# SCHEMA.net
KiCad netlist of a schematic drawn in EAGLE
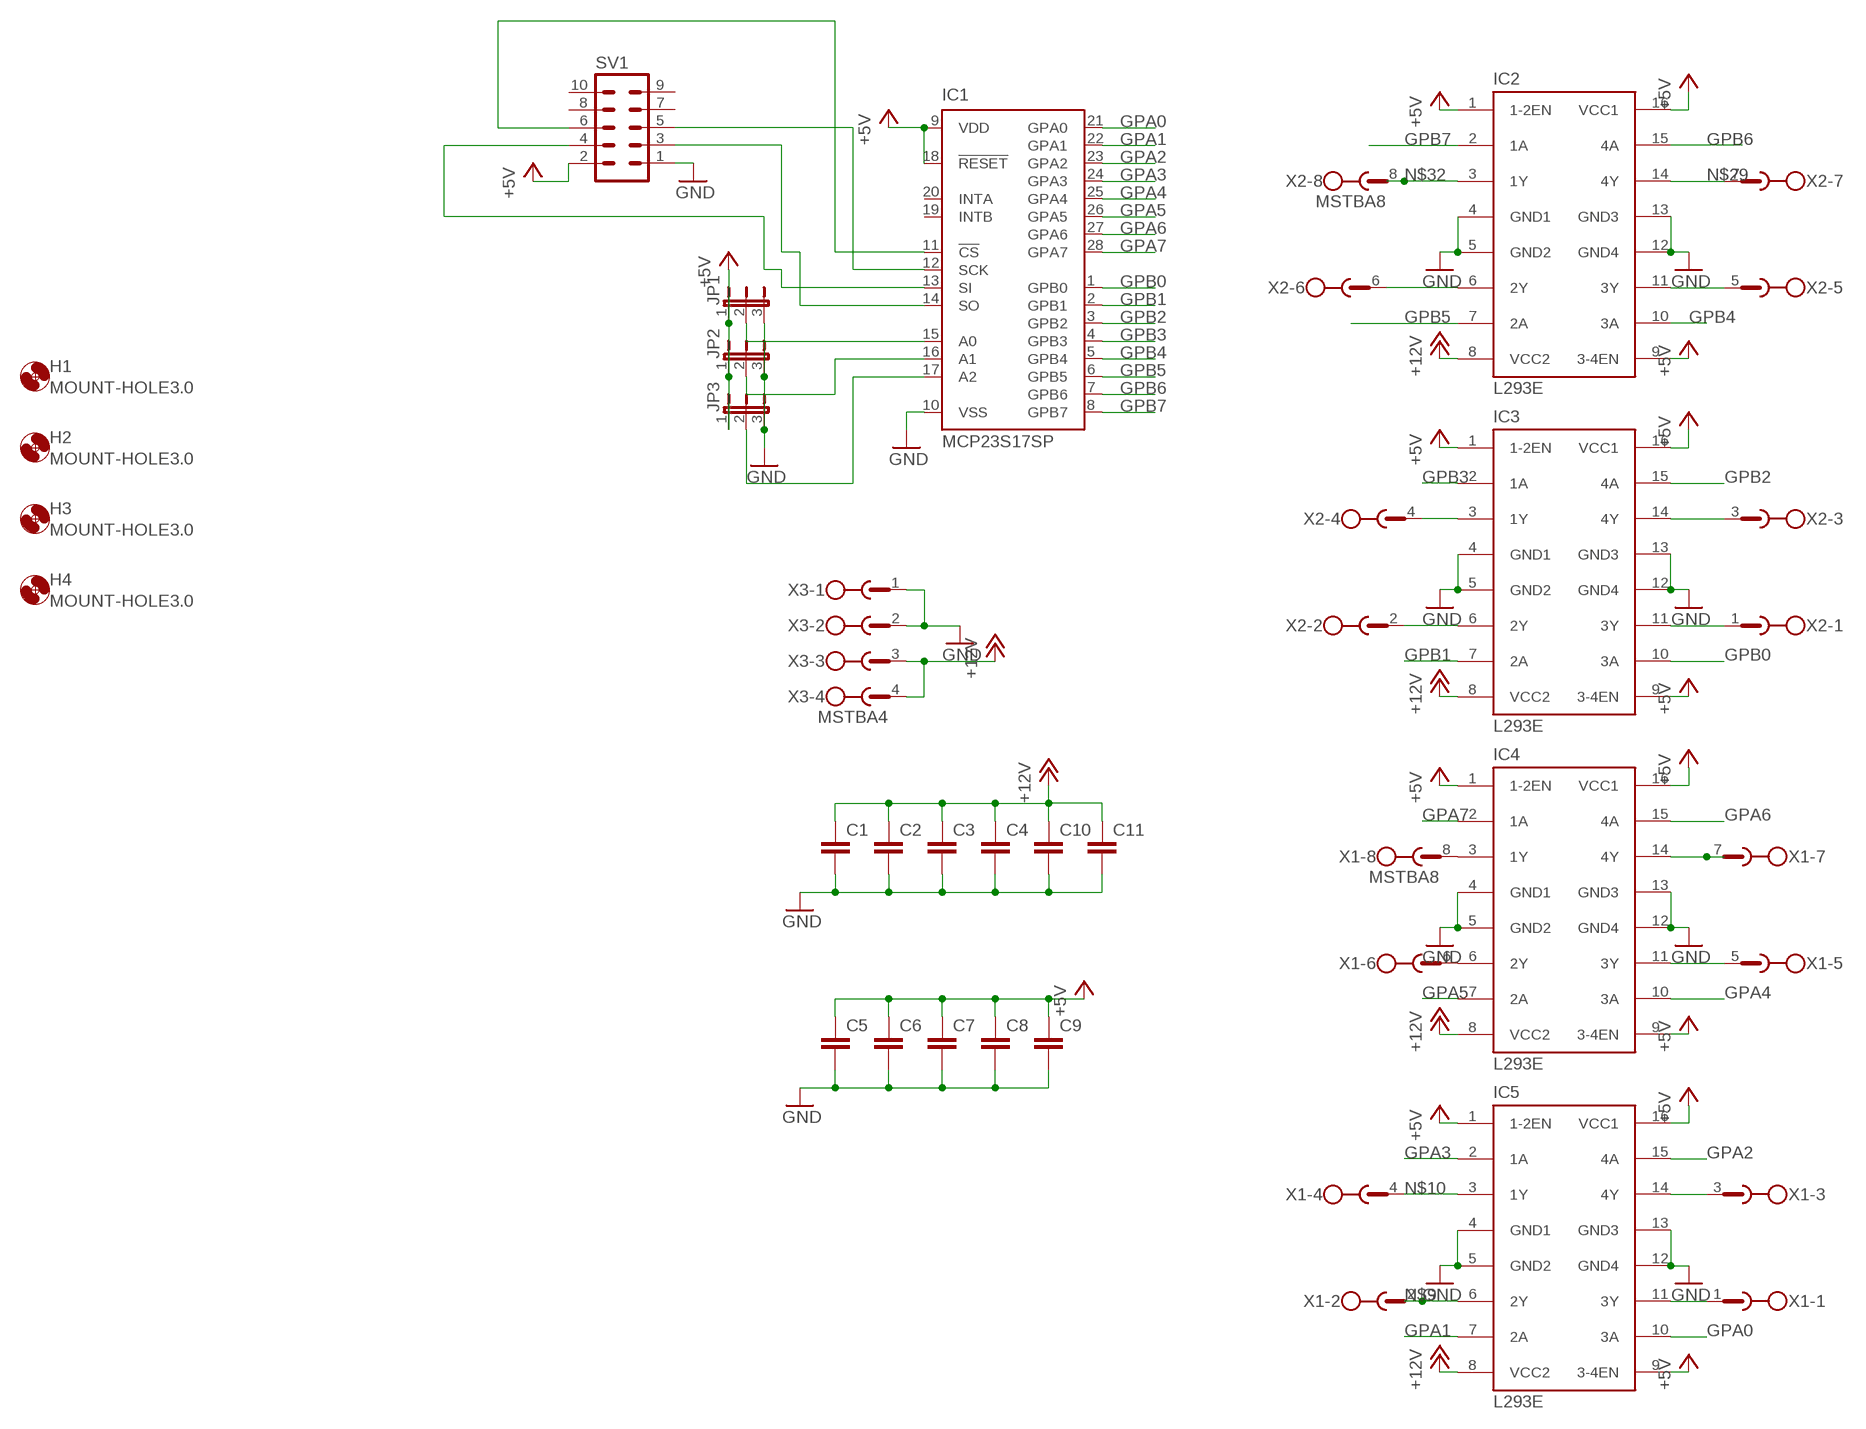
[diagram p0: schematic, sheet 1]

(export (version "E")
  (design (tool "Eeschema 10.0.6"))
  (components
    (comp (ref "C1")
      (value "C-EU025-025X050")
      (footprint "eagle-import:C025-025X050")
      (libsource (lib "eagle-import") (part "C-EU025-025X050"))
    )
    (comp (ref "C2")
      (value "C-EU025-025X050")
      (footprint "eagle-import:C025-025X050")
      (libsource (lib "eagle-import") (part "C-EU025-025X050"))
    )
    (comp (ref "C3")
      (value "C-EU025-025X050")
      (footprint "eagle-import:C025-025X050")
      (libsource (lib "eagle-import") (part "C-EU025-025X050"))
    )
    (comp (ref "C4")
      (value "C-EU025-025X050")
      (footprint "eagle-import:C025-025X050")
      (libsource (lib "eagle-import") (part "C-EU025-025X050"))
    )
    (comp (ref "C5")
      (value "C-EU025-025X050")
      (footprint "eagle-import:C025-025X050")
      (libsource (lib "eagle-import") (part "C-EU025-025X050"))
    )
    (comp (ref "C6")
      (value "C-EU025-025X050")
      (footprint "eagle-import:C025-025X050")
      (libsource (lib "eagle-import") (part "C-EU025-025X050"))
    )
    (comp (ref "C7")
      (value "C-EU025-025X050")
      (footprint "eagle-import:C025-025X050")
      (libsource (lib "eagle-import") (part "C-EU025-025X050"))
    )
    (comp (ref "C8")
      (value "C-EU025-025X050")
      (footprint "eagle-import:C025-025X050")
      (libsource (lib "eagle-import") (part "C-EU025-025X050"))
    )
    (comp (ref "C9")
      (value "C-EU025-025X050")
      (footprint "eagle-import:C025-025X050")
      (libsource (lib "eagle-import") (part "C-EU025-025X050"))
    )
    (comp (ref "C10")
      (value "C-EU025-025X050")
      (footprint "eagle-import:C025-025X050")
      (libsource (lib "eagle-import") (part "C-EU025-025X050"))
    )
    (comp (ref "C11")
      (value "C-EU025-025X050")
      (footprint "eagle-import:C025-025X050")
      (libsource (lib "eagle-import") (part "C-EU025-025X050"))
    )
    (comp (ref "H1")
      (value "MOUNT-HOLE3.0")
      (footprint "eagle-import:3,0")
      (libsource (lib "eagle-import") (part "MOUNT-HOLE3.0"))
    )
    (comp (ref "H2")
      (value "MOUNT-HOLE3.0")
      (footprint "eagle-import:3,0")
      (libsource (lib "eagle-import") (part "MOUNT-HOLE3.0"))
    )
    (comp (ref "H3")
      (value "MOUNT-HOLE3.0")
      (footprint "eagle-import:3,0")
      (libsource (lib "eagle-import") (part "MOUNT-HOLE3.0"))
    )
    (comp (ref "H4")
      (value "MOUNT-HOLE3.0")
      (footprint "eagle-import:3,0")
      (libsource (lib "eagle-import") (part "MOUNT-HOLE3.0"))
    )
    (comp (ref "IC1")
      (value "MCP23S17SP")
      (footprint "eagle-import:DIL28-3")
      (fields (field (name "MF") "MICROCHIP") (field (name "MPN") "MCP23S17-E/SP"))
      (libsource (lib "eagle-import") (part "MCP23S17SP"))
    )
    (comp (ref "IC2")
      (value "L293E")
      (footprint "eagle-import:DIL16")
      (fields (field (name "MF") "Arrow Electronics"))
      (libsource (lib "eagle-import") (part "L293E"))
    )
    (comp (ref "IC3")
      (value "L293E")
      (footprint "eagle-import:DIL16")
      (fields (field (name "MF") "Arrow Electronics"))
      (libsource (lib "eagle-import") (part "L293E"))
    )
    (comp (ref "IC4")
      (value "L293E")
      (footprint "eagle-import:DIL16")
      (fields (field (name "MF") "Arrow Electronics"))
      (libsource (lib "eagle-import") (part "L293E"))
    )
    (comp (ref "IC5")
      (value "L293E")
      (footprint "eagle-import:DIL16")
      (fields (field (name "MF") "Arrow Electronics"))
      (libsource (lib "eagle-import") (part "L293E"))
    )
    (comp (ref "JP1")
      (value "JP2E")
      (footprint "eagle-import:JP2")
      (libsource (lib "eagle-import") (part "JP2E"))
    )
    (comp (ref "JP2")
      (value "JP2E")
      (footprint "eagle-import:JP2")
      (libsource (lib "eagle-import") (part "JP2E"))
    )
    (comp (ref "JP3")
      (value "JP2E")
      (footprint "eagle-import:JP2")
      (libsource (lib "eagle-import") (part "JP2E"))
    )
    (comp (ref "SV1")
      (value "ML10")
      (footprint "eagle-import:ML10")
      (libsource (lib "eagle-import") (part "ML10"))
    )
    (comp (ref "X1")
      (value "MSTBA8")
      (footprint "eagle-import:MSTBA8")
      (fields (field (name "MF") "FARNELL") (field (name "MPN") "1757307"))
      (libsource (lib "eagle-import") (part "MSTBA8"))
    )
    (comp (ref "X2")
      (value "MSTBA8")
      (footprint "eagle-import:MSTBA8")
      (fields (field (name "MF") "FARNELL") (field (name "MPN") "1757307"))
      (libsource (lib "eagle-import") (part "MSTBA8"))
    )
    (comp (ref "X3")
      (value "MSTBA4")
      (footprint "eagle-import:MSTBA4")
      (fields (field (name "MF") "FARNELL") (field (name "MPN") "1757268"))
      (libsource (lib "eagle-import") (part "MSTBA4"))
    )
  )
  (nets
    (net (code "1") (name "+5V") (class "Default")
      (node (ref "C5") (pin "1") (pinfunction "1_1") (pintype "passive"))
      (node (ref "C6") (pin "1") (pinfunction "1_1") (pintype "passive"))
      (node (ref "C7") (pin "1") (pinfunction "1_1") (pintype "passive"))
      (node (ref "C8") (pin "1") (pinfunction "1_1") (pintype "passive"))
      (node (ref "C9") (pin "1") (pinfunction "1_1") (pintype "passive"))
      (node (ref "IC1") (pin "18") (pinfunction "~{RESET}_18") (pintype "input"))
      (node (ref "IC1") (pin "9") (pinfunction "VDD_9") (pintype "power_in"))
      (node (ref "IC2") (pin "1") (pinfunction "1-2EN_1") (pintype "input"))
      (node (ref "IC2") (pin "16") (pinfunction "VCC1_16") (pintype "power_in"))
      (node (ref "IC2") (pin "9") (pinfunction "3-4EN_9") (pintype "input"))
      (node (ref "IC3") (pin "1") (pinfunction "1-2EN_1") (pintype "input"))
      (node (ref "IC3") (pin "16") (pinfunction "VCC1_16") (pintype "power_in"))
      (node (ref "IC3") (pin "9") (pinfunction "3-4EN_9") (pintype "input"))
      (node (ref "IC4") (pin "1") (pinfunction "1-2EN_1") (pintype "input"))
      (node (ref "IC4") (pin "16") (pinfunction "VCC1_16") (pintype "power_in"))
      (node (ref "IC4") (pin "9") (pinfunction "3-4EN_9") (pintype "input"))
      (node (ref "IC5") (pin "1") (pinfunction "1-2EN_1") (pintype "input"))
      (node (ref "IC5") (pin "16") (pinfunction "VCC1_16") (pintype "power_in"))
      (node (ref "IC5") (pin "9") (pinfunction "3-4EN_9") (pintype "input"))
      (node (ref "JP1") (pin "1") (pinfunction "1_1") (pintype "passive"))
      (node (ref "JP2") (pin "1") (pinfunction "1_1") (pintype "passive"))
      (node (ref "JP3") (pin "1") (pinfunction "1_1") (pintype "passive"))
      (node (ref "SV1") (pin "2") (pinfunction "2_2") (pintype "passive"))
    )
    (net (code "2") (name "+12V") (class "Default")
      (node (ref "C1") (pin "1") (pinfunction "1_1") (pintype "passive"))
      (node (ref "C10") (pin "1") (pinfunction "1_1") (pintype "passive"))
      (node (ref "C11") (pin "1") (pinfunction "1_1") (pintype "passive"))
      (node (ref "C2") (pin "1") (pinfunction "1_1") (pintype "passive"))
      (node (ref "C3") (pin "1") (pinfunction "1_1") (pintype "passive"))
      (node (ref "C4") (pin "1") (pinfunction "1_1") (pintype "passive"))
      (node (ref "IC2") (pin "8") (pinfunction "VCC2_8") (pintype "power_in"))
      (node (ref "IC3") (pin "8") (pinfunction "VCC2_8") (pintype "power_in"))
      (node (ref "IC4") (pin "8") (pinfunction "VCC2_8") (pintype "power_in"))
      (node (ref "IC5") (pin "8") (pinfunction "VCC2_8") (pintype "power_in"))
      (node (ref "X3") (pin "3") (pinfunction "1_3") (pintype "passive"))
      (node (ref "X3") (pin "4") (pinfunction "1_4") (pintype "passive"))
    )
    (net (code "3") (name "/GPA0") (class "Default")
      (node (ref "IC1") (pin "21") (pinfunction "GPA0_21") (pintype "bidirectional"))
      (node (ref "IC5") (pin "10") (pinfunction "3A_10") (pintype "input"))
    )
    (net (code "4") (name "/GPA1") (class "Default")
      (node (ref "IC1") (pin "22") (pinfunction "GPA1_22") (pintype "bidirectional"))
      (node (ref "IC5") (pin "7") (pinfunction "2A_7") (pintype "input"))
    )
    (net (code "5") (name "/GPA2") (class "Default")
      (node (ref "IC1") (pin "23") (pinfunction "GPA2_23") (pintype "bidirectional"))
      (node (ref "IC5") (pin "15") (pinfunction "4A_15") (pintype "input"))
    )
    (net (code "6") (name "/GPA3") (class "Default")
      (node (ref "IC1") (pin "24") (pinfunction "GPA3_24") (pintype "bidirectional"))
      (node (ref "IC5") (pin "2") (pinfunction "1A_2") (pintype "input"))
    )
    (net (code "7") (name "/GPA4") (class "Default")
      (node (ref "IC1") (pin "25") (pinfunction "GPA4_25") (pintype "bidirectional"))
      (node (ref "IC4") (pin "10") (pinfunction "3A_10") (pintype "input"))
    )
    (net (code "8") (name "/GPA5") (class "Default")
      (node (ref "IC1") (pin "26") (pinfunction "GPA5_26") (pintype "bidirectional"))
      (node (ref "IC4") (pin "7") (pinfunction "2A_7") (pintype "input"))
    )
    (net (code "9") (name "/GPA6") (class "Default")
      (node (ref "IC1") (pin "27") (pinfunction "GPA6_27") (pintype "bidirectional"))
      (node (ref "IC4") (pin "15") (pinfunction "4A_15") (pintype "input"))
    )
    (net (code "10") (name "/GPA7") (class "Default")
      (node (ref "IC1") (pin "28") (pinfunction "GPA7_28") (pintype "bidirectional"))
      (node (ref "IC4") (pin "2") (pinfunction "1A_2") (pintype "input"))
    )
    (net (code "11") (name "/GPB0") (class "Default")
      (node (ref "IC1") (pin "1") (pinfunction "GPB0_1") (pintype "bidirectional"))
      (node (ref "IC3") (pin "10") (pinfunction "3A_10") (pintype "input"))
    )
    (net (code "12") (name "/GPB1") (class "Default")
      (node (ref "IC1") (pin "2") (pinfunction "GPB1_2") (pintype "bidirectional"))
      (node (ref "IC3") (pin "7") (pinfunction "2A_7") (pintype "input"))
    )
    (net (code "13") (name "/GPB2") (class "Default")
      (node (ref "IC1") (pin "3") (pinfunction "GPB2_3") (pintype "bidirectional"))
      (node (ref "IC3") (pin "15") (pinfunction "4A_15") (pintype "input"))
    )
    (net (code "14") (name "/GPB3") (class "Default")
      (node (ref "IC1") (pin "4") (pinfunction "GPB3_4") (pintype "bidirectional"))
      (node (ref "IC3") (pin "2") (pinfunction "1A_2") (pintype "input"))
    )
    (net (code "15") (name "/GPB4") (class "Default")
      (node (ref "IC1") (pin "5") (pinfunction "GPB4_5") (pintype "bidirectional"))
      (node (ref "IC2") (pin "10") (pinfunction "3A_10") (pintype "input"))
    )
    (net (code "16") (name "/GPB5") (class "Default")
      (node (ref "IC1") (pin "6") (pinfunction "GPB5_6") (pintype "bidirectional"))
      (node (ref "IC2") (pin "7") (pinfunction "2A_7") (pintype "input"))
    )
    (net (code "17") (name "/GPB6") (class "Default")
      (node (ref "IC1") (pin "7") (pinfunction "GPB6_7") (pintype "bidirectional"))
      (node (ref "IC2") (pin "15") (pinfunction "4A_15") (pintype "input"))
    )
    (net (code "18") (name "/GPB7") (class "Default")
      (node (ref "IC1") (pin "8") (pinfunction "GPB7_8") (pintype "bidirectional"))
      (node (ref "IC2") (pin "2") (pinfunction "1A_2") (pintype "input"))
    )
    (net (code "19") (name "/N$9") (class "Default")
      (node (ref "IC5") (pin "6") (pinfunction "2Y_6") (pintype "output"))
      (node (ref "X1") (pin "2") (pinfunction "1_2") (pintype "passive"))
    )
    (net (code "20") (name "/N$10") (class "Default")
      (node (ref "IC5") (pin "3") (pinfunction "1Y_3") (pintype "output"))
      (node (ref "X1") (pin "4") (pinfunction "1_4") (pintype "passive"))
    )
    (net (code "21") (name "/N$29") (class "Default")
      (node (ref "IC2") (pin "14") (pinfunction "4Y_14") (pintype "output"))
      (node (ref "X2") (pin "7") (pinfunction "1_7") (pintype "passive"))
    )
    (net (code "22") (name "/N$32") (class "Default")
      (node (ref "IC2") (pin "3") (pinfunction "1Y_3") (pintype "output"))
      (node (ref "X2") (pin "8") (pinfunction "1_8") (pintype "passive"))
    )
    (net (code "23") (name "GND") (class "Default")
      (node (ref "C1") (pin "2") (pinfunction "2_2") (pintype "passive"))
      (node (ref "C10") (pin "2") (pinfunction "2_2") (pintype "passive"))
      (node (ref "C11") (pin "2") (pinfunction "2_2") (pintype "passive"))
      (node (ref "C2") (pin "2") (pinfunction "2_2") (pintype "passive"))
      (node (ref "C3") (pin "2") (pinfunction "2_2") (pintype "passive"))
      (node (ref "C4") (pin "2") (pinfunction "2_2") (pintype "passive"))
      (node (ref "C5") (pin "2") (pinfunction "2_2") (pintype "passive"))
      (node (ref "C6") (pin "2") (pinfunction "2_2") (pintype "passive"))
      (node (ref "C7") (pin "2") (pinfunction "2_2") (pintype "passive"))
      (node (ref "C8") (pin "2") (pinfunction "2_2") (pintype "passive"))
      (node (ref "C9") (pin "2") (pinfunction "2_2") (pintype "passive"))
      (node (ref "IC1") (pin "10") (pinfunction "VSS_10") (pintype "power_in"))
      (node (ref "IC2") (pin "12") (pinfunction "GND4_12") (pintype "power_in"))
      (node (ref "IC2") (pin "13") (pinfunction "GND3_13") (pintype "power_in"))
      (node (ref "IC2") (pin "4") (pinfunction "GND1_4") (pintype "power_in"))
      (node (ref "IC2") (pin "5") (pinfunction "GND2_5") (pintype "power_in"))
      (node (ref "IC3") (pin "12") (pinfunction "GND4_12") (pintype "power_in"))
      (node (ref "IC3") (pin "13") (pinfunction "GND3_13") (pintype "power_in"))
      (node (ref "IC3") (pin "4") (pinfunction "GND1_4") (pintype "power_in"))
      (node (ref "IC3") (pin "5") (pinfunction "GND2_5") (pintype "power_in"))
      (node (ref "IC4") (pin "12") (pinfunction "GND4_12") (pintype "power_in"))
      (node (ref "IC4") (pin "13") (pinfunction "GND3_13") (pintype "power_in"))
      (node (ref "IC4") (pin "4") (pinfunction "GND1_4") (pintype "power_in"))
      (node (ref "IC4") (pin "5") (pinfunction "GND2_5") (pintype "power_in"))
      (node (ref "IC5") (pin "12") (pinfunction "GND4_12") (pintype "power_in"))
      (node (ref "IC5") (pin "13") (pinfunction "GND3_13") (pintype "power_in"))
      (node (ref "IC5") (pin "4") (pinfunction "GND1_4") (pintype "power_in"))
      (node (ref "IC5") (pin "5") (pinfunction "GND2_5") (pintype "power_in"))
      (node (ref "JP1") (pin "3") (pinfunction "3_3") (pintype "passive"))
      (node (ref "JP2") (pin "3") (pinfunction "3_3") (pintype "passive"))
      (node (ref "JP3") (pin "3") (pinfunction "3_3") (pintype "passive"))
      (node (ref "SV1") (pin "1") (pinfunction "1_1") (pintype "passive"))
      (node (ref "X3") (pin "1") (pinfunction "1_1") (pintype "passive"))
      (node (ref "X3") (pin "2") (pinfunction "1_2") (pintype "passive"))
    )
    (net (code "24") (name "Net-(IC1-A0)") (class "Default")
      (node (ref "IC1") (pin "15") (pinfunction "A0_15") (pintype "input"))
      (node (ref "JP1") (pin "2") (pinfunction "2_2") (pintype "passive"))
    )
    (net (code "25") (name "Net-(IC1-A1)") (class "Default")
      (node (ref "IC1") (pin "16") (pinfunction "A1_16") (pintype "input"))
      (node (ref "JP2") (pin "2") (pinfunction "2_2") (pintype "passive"))
    )
    (net (code "26") (name "Net-(IC1-A2)") (class "Default")
      (node (ref "IC1") (pin "17") (pinfunction "A2_17") (pintype "input"))
      (node (ref "JP3") (pin "2") (pinfunction "2_2") (pintype "passive"))
    )
    (net (code "27") (name "Net-(IC1-SCK)") (class "Default")
      (node (ref "IC1") (pin "12") (pinfunction "SCK_12") (pintype "input"))
      (node (ref "SV1") (pin "5") (pinfunction "5_5") (pintype "passive"))
    )
    (net (code "28") (name "Net-(IC1-SI)") (class "Default")
      (node (ref "IC1") (pin "13") (pinfunction "SI_13") (pintype "input"))
      (node (ref "SV1") (pin "4") (pinfunction "4_4") (pintype "passive"))
    )
    (net (code "29") (name "Net-(IC1-SO)") (class "Default")
      (node (ref "IC1") (pin "14") (pinfunction "SO_14") (pintype "output"))
      (node (ref "SV1") (pin "3") (pinfunction "3_3") (pintype "passive"))
    )
    (net (code "30") (name "Net-(IC1-~{CS})") (class "Default")
      (node (ref "IC1") (pin "11") (pinfunction "~{CS}_11") (pintype "input"))
      (node (ref "SV1") (pin "6") (pinfunction "6_6") (pintype "passive"))
    )
    (net (code "31") (name "Net-(IC2-2Y)") (class "Default")
      (node (ref "IC2") (pin "6") (pinfunction "2Y_6") (pintype "output"))
      (node (ref "X2") (pin "6") (pinfunction "1_6") (pintype "passive"))
    )
    (net (code "32") (name "Net-(IC2-3Y)") (class "Default")
      (node (ref "IC2") (pin "11") (pinfunction "3Y_11") (pintype "output"))
      (node (ref "X2") (pin "5") (pinfunction "1_5") (pintype "passive"))
    )
    (net (code "33") (name "Net-(IC3-1Y)") (class "Default")
      (node (ref "IC3") (pin "3") (pinfunction "1Y_3") (pintype "output"))
      (node (ref "X2") (pin "4") (pinfunction "1_4") (pintype "passive"))
    )
    (net (code "34") (name "Net-(IC3-2Y)") (class "Default")
      (node (ref "IC3") (pin "6") (pinfunction "2Y_6") (pintype "output"))
      (node (ref "X2") (pin "2") (pinfunction "1_2") (pintype "passive"))
    )
    (net (code "35") (name "Net-(IC3-3Y)") (class "Default")
      (node (ref "IC3") (pin "11") (pinfunction "3Y_11") (pintype "output"))
      (node (ref "X2") (pin "1") (pinfunction "1_1") (pintype "passive"))
    )
    (net (code "36") (name "Net-(IC3-4Y)") (class "Default")
      (node (ref "IC3") (pin "14") (pinfunction "4Y_14") (pintype "output"))
      (node (ref "X2") (pin "3") (pinfunction "1_3") (pintype "passive"))
    )
    (net (code "37") (name "Net-(IC4-1Y)") (class "Default")
      (node (ref "IC4") (pin "3") (pinfunction "1Y_3") (pintype "output"))
      (node (ref "X1") (pin "8") (pinfunction "1_8") (pintype "passive"))
    )
    (net (code "38") (name "Net-(IC4-2Y)") (class "Default")
      (node (ref "IC4") (pin "6") (pinfunction "2Y_6") (pintype "output"))
      (node (ref "X1") (pin "6") (pinfunction "1_6") (pintype "passive"))
    )
    (net (code "39") (name "Net-(IC4-3Y)") (class "Default")
      (node (ref "IC4") (pin "11") (pinfunction "3Y_11") (pintype "output"))
      (node (ref "X1") (pin "5") (pinfunction "1_5") (pintype "passive"))
    )
    (net (code "40") (name "Net-(IC4-4Y)") (class "Default")
      (node (ref "IC4") (pin "14") (pinfunction "4Y_14") (pintype "output"))
      (node (ref "X1") (pin "7") (pinfunction "1_7") (pintype "passive"))
    )
    (net (code "41") (name "Net-(IC5-3Y)") (class "Default")
      (node (ref "IC5") (pin "11") (pinfunction "3Y_11") (pintype "output"))
      (node (ref "X1") (pin "1") (pinfunction "1_1") (pintype "passive"))
    )
    (net (code "42") (name "Net-(IC5-4Y)") (class "Default")
      (node (ref "IC5") (pin "14") (pinfunction "4Y_14") (pintype "output"))
      (node (ref "X1") (pin "3") (pinfunction "1_3") (pintype "passive"))
    )
    (net (code "43") (name "unconnected-(IC1-INTA-Pad20)") (class "Default")
      (node (ref "IC1") (pin "20") (pinfunction "INTA_20") (pintype "output"))
    )
    (net (code "44") (name "unconnected-(IC1-INTB-Pad19)") (class "Default")
      (node (ref "IC1") (pin "19") (pinfunction "INTB_19") (pintype "output"))
    )
    (net (code "45") (name "unconnected-(SV1-Pad7)") (class "Default")
      (node (ref "SV1") (pin "7") (pinfunction "7_7") (pintype "passive"))
    )
    (net (code "46") (name "unconnected-(SV1-Pad8)") (class "Default")
      (node (ref "SV1") (pin "8") (pinfunction "8_8") (pintype "passive"))
    )
    (net (code "47") (name "unconnected-(SV1-Pad9)") (class "Default")
      (node (ref "SV1") (pin "9") (pinfunction "9_9") (pintype "passive"))
    )
    (net (code "48") (name "unconnected-(SV1-Pad10)") (class "Default")
      (node (ref "SV1") (pin "10") (pinfunction "10_10") (pintype "passive"))
    )
  )
)
